# WL-CONTROL.net
KiCad netlist of a schematic drawn in Altium Designer
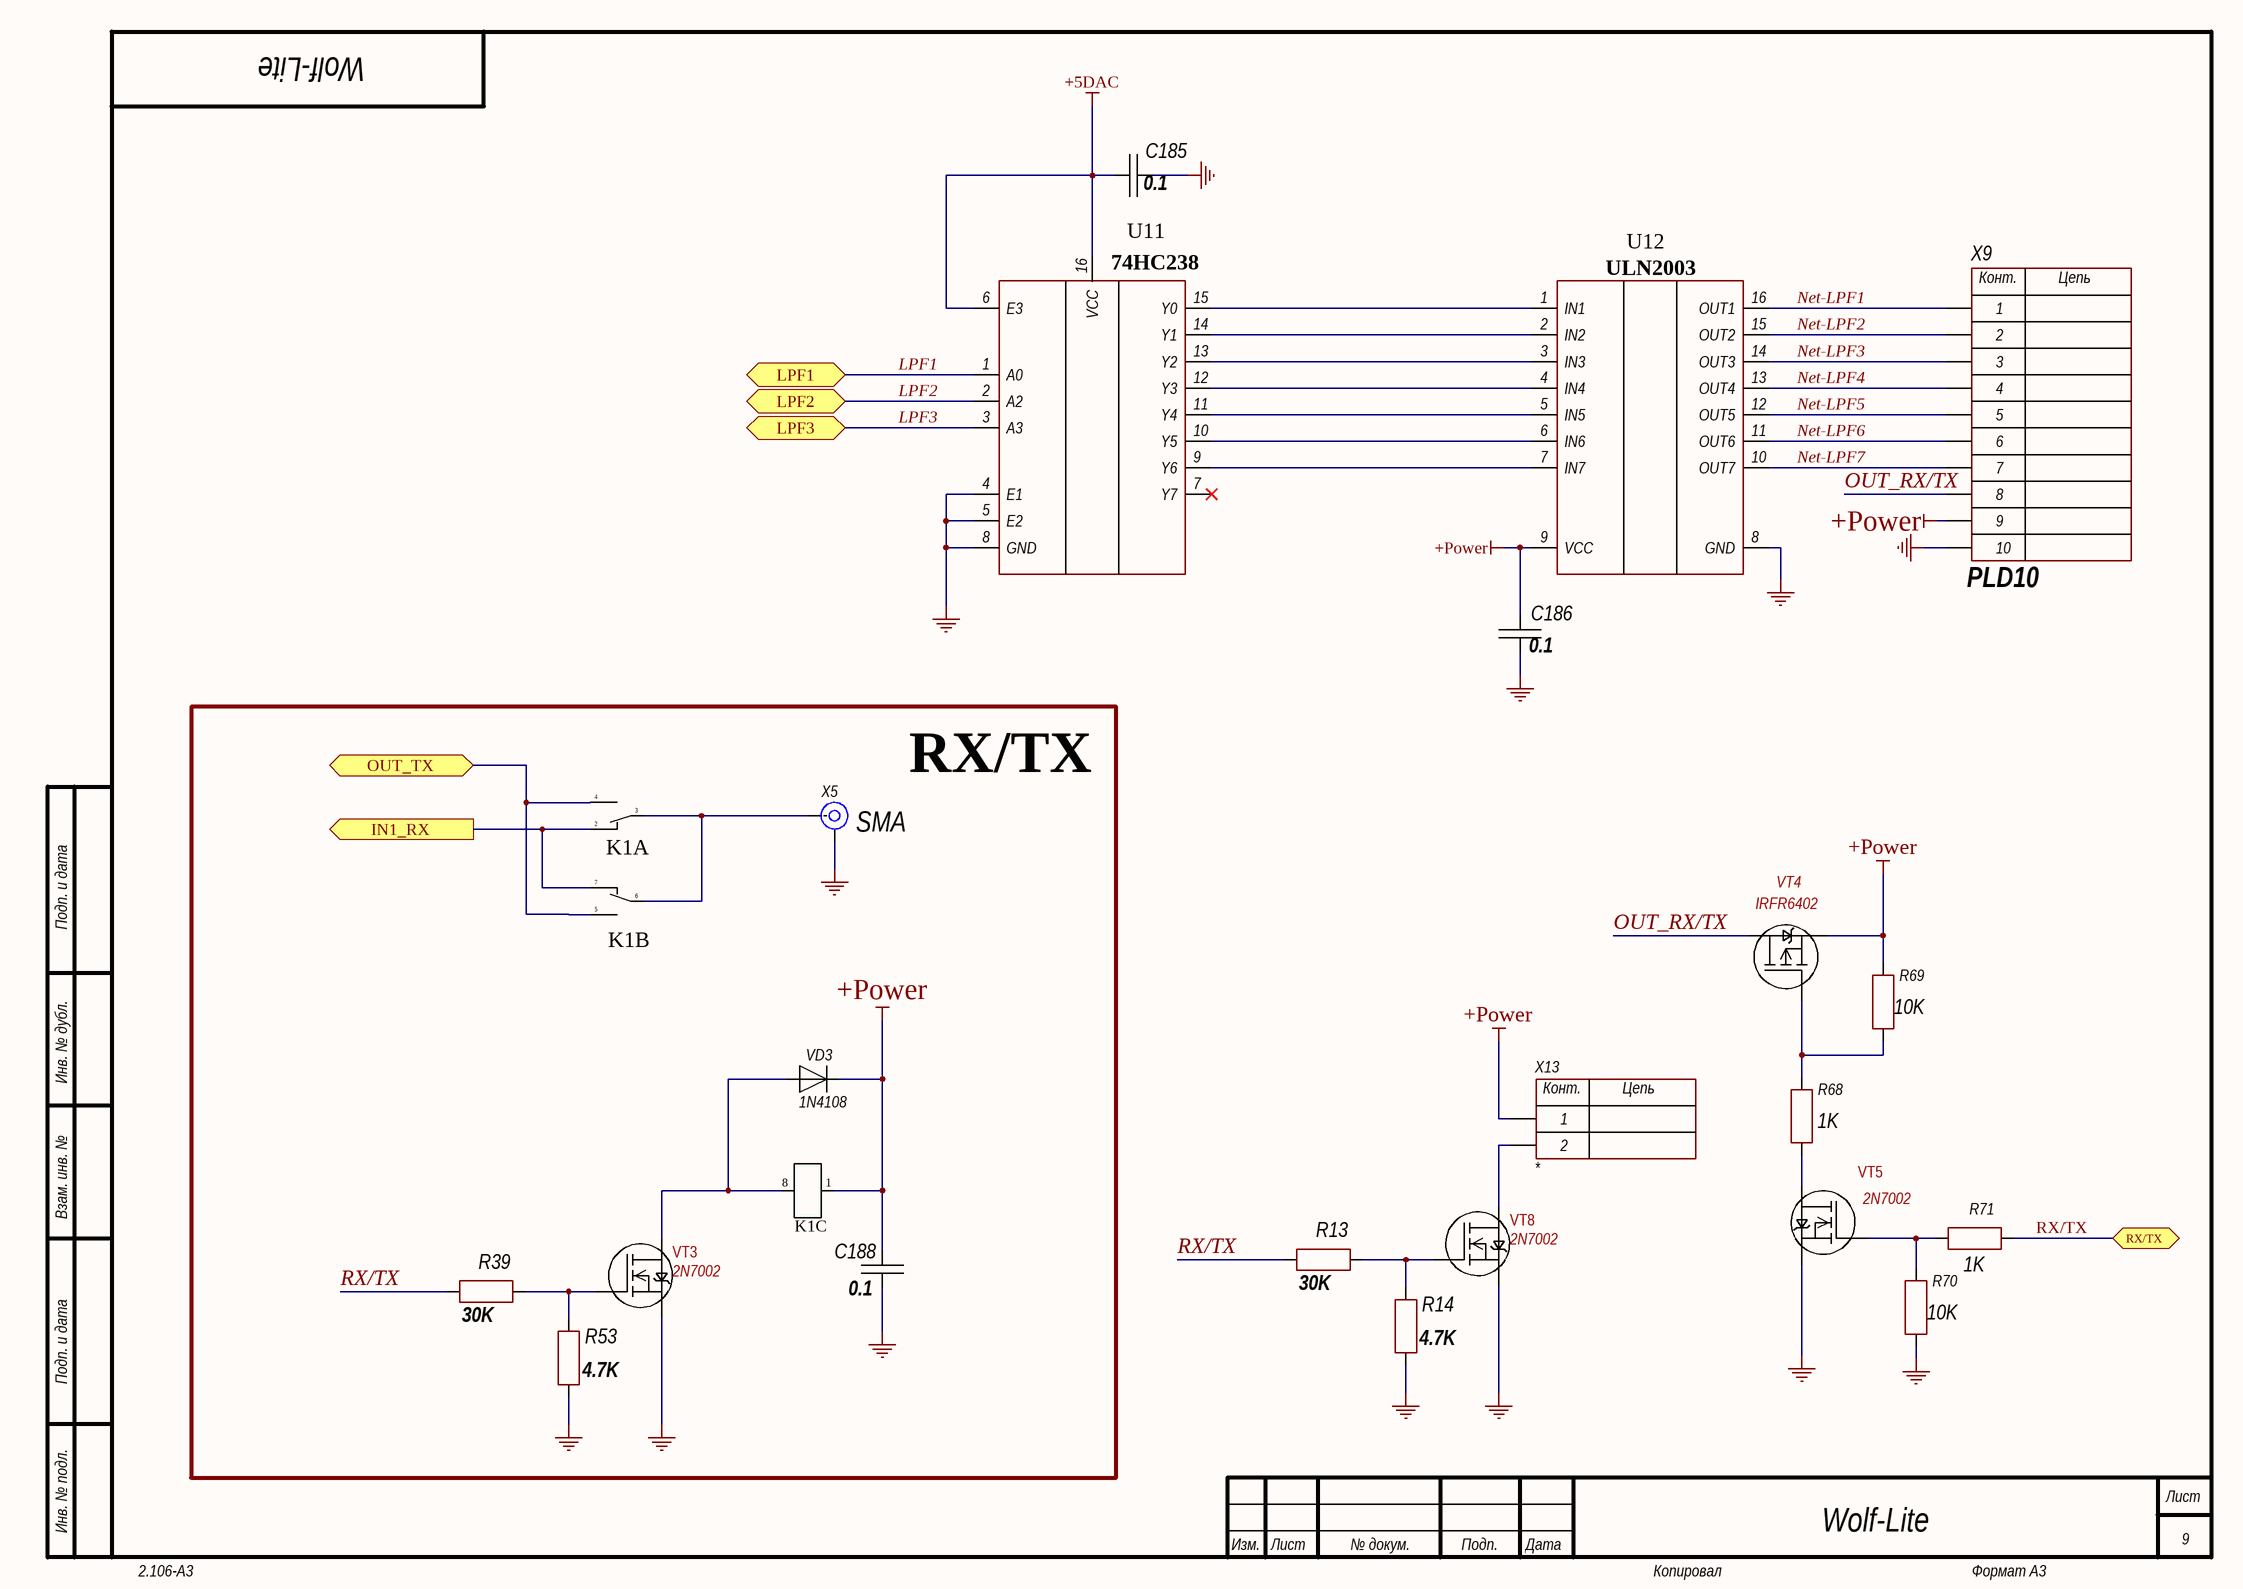
[diagram p0: WL-CONTROL.SchDoc]

(export (version "E")
  (design (tool "Eeschema 10.0.6"))
  (components
    (comp (ref "C185")
      (value "0.1")
      (footprint "standard:CH0805C")
      (libsource (lib "Discrete") (part "Capacitor"))
    )
    (comp (ref "C186")
      (value "0.1")
      (footprint "standard:CH0805C")
      (libsource (lib "Discrete") (part "Capacitor"))
    )
    (comp (ref "C188")
      (value "0.1")
      (footprint "standard:CH0805C")
      (libsource (lib "Discrete") (part "Capacitor"))
    )
    (comp (ref "K1") (value "IM06") (footprint "IMG06") (libsource (lib "") (part "IM06-1_1")))
    (comp (ref "R13")
      (value "30K")
      (footprint "standard:CH0805R")
      (libsource (lib "Discrete") (part "Resistor"))
    )
    (comp (ref "R14") (value "4.7K") (footprint "standard:CH0805R") (libsource (lib "") (part "Resistor_1")))
    (comp (ref "R39")
      (value "30K")
      (footprint "standard:CH0805R")
      (libsource (lib "Discrete") (part "Resistor"))
    )
    (comp (ref "R53") (value "4.7K") (footprint "standard:CH0805R") (libsource (lib "") (part "Resistor_1")))
    (comp (ref "R68") (value "1K") (footprint "standard:CH0805R") (libsource (lib "") (part "Resistor_1")))
    (comp (ref "R69") (value "10K") (footprint "standard:CH0805R") (libsource (lib "") (part "Resistor_1")))
    (comp (ref "R70") (value "10K") (footprint "standard:CH0805R") (libsource (lib "") (part "Resistor_1")))
    (comp (ref "R71")
      (value "1K")
      (footprint "standard:CH0805R")
      (libsource (lib "Discrete") (part "Resistor"))
    )
    (comp (ref "U11") (value "74HC238") (footprint "16-SOIC") (libsource (lib "Digital") (part "74HC238")))
    (comp (ref "U12")
      (value "ULN2003")
      (footprint "16-SOIC")
      (libsource (lib "Digital") (part "ULN2003_NEW"))
    )
    (comp (ref "VD3") (value "1N4108") (footprint "1N4148") (libsource (lib "Diods") (part "Diod")))
    (comp (ref "VT3")
      (value "2N7002")
      (footprint "SOT23_132")
      (libsource (lib "Transistor") (part "N-KANAL"))
    )
    (comp (ref "VT4")
      (value "IRFR6402")
      (footprint "SOT23_132")
      (libsource (lib "Transistor") (part "P-KANAL"))
    )
    (comp (ref "VT5") (value "2N7002") (footprint "SOT23_132") (libsource (lib "") (part "N-KANAL_1")))
    (comp (ref "VT8")
      (value "2N7002")
      (footprint "SOT23_132")
      (libsource (lib "Transistor") (part "N-KANAL"))
    )
    (comp (ref "X5")
      (value "SMA")
      (footprint "custom:CON: SMA")
      (description "RF")
      (libsource (lib "Connectors") (part "SMA"))
    )
    (comp (ref "X9")
      (value "PLD10")
      (footprint "custom:CON: PLD-10")
      (libsource (lib "Connectors") (part "10-Connector"))
    )
    (comp (ref "X13")
      (value "*")
      (footprint "custom:CON: PLS-2")
      (libsource (lib "Connectors") (part "2-Connector"))
    )
  )
  (nets
    (net (code "1") (name "+5DAC") (class "Default")
      (node (ref "C185") (pin "1") (pinfunction "1_1") (pintype "power_in"))
      (node (ref "U11") (pin "16") (pinfunction "VCC_16") (pintype "passive"))
      (node (ref "U11") (pin "6") (pinfunction "E3_6") (pintype "passive"))
    )
    (net (code "2") (name "+Power") (class "Default")
      (node (ref "C186") (pin "2") (pinfunction "2_2") (pintype "power_in"))
      (node (ref "C188") (pin "1") (pinfunction "1_1") (pintype "power_in"))
      (node (ref "K1") (pin "1") (pintype "passive"))
      (node (ref "R69") (pin "2") (pinfunction "2_2") (pintype "passive"))
      (node (ref "U12") (pin "9") (pinfunction "VCC_9") (pintype "passive"))
      (node (ref "VD3") (pin "2") (pinfunction "2_2") (pintype "passive"))
      (node (ref "VT4") (pin "2") (pinfunction "I_2") (pintype "passive"))
      (node (ref "X13") (pin "1") (pinfunction "1_1") (pintype "passive"))
      (node (ref "X9") (pin "9") (pinfunction "9_9") (pintype "power_in"))
    )
    (net (code "3") (name "/IN1_RX") (class "Default")
      (node (ref "K1") (pin "2") (pintype "passive"))
      (node (ref "K1") (pin "7") (pintype "passive"))
    )
    (net (code "4") (name "/LPF1") (class "Default")
      (node (ref "U11") (pin "1") (pinfunction "A0_1") (pintype "passive"))
    )
    (net (code "5") (name "/LPF2") (class "Default")
      (node (ref "U11") (pin "2") (pinfunction "A2_2") (pintype "passive"))
    )
    (net (code "6") (name "/LPF3") (class "Default")
      (node (ref "U11") (pin "3") (pinfunction "A3_3") (pintype "passive"))
    )
    (net (code "7") (name "/Net-LPF1") (class "Default")
      (node (ref "U12") (pin "16") (pinfunction "OUT1_16") (pintype "passive"))
      (node (ref "X9") (pin "1") (pinfunction "1_1") (pintype "passive"))
    )
    (net (code "8") (name "/Net-LPF2") (class "Default")
      (node (ref "U12") (pin "15") (pinfunction "OUT2_15") (pintype "passive"))
      (node (ref "X9") (pin "2") (pinfunction "2_2") (pintype "passive"))
    )
    (net (code "9") (name "/Net-LPF3") (class "Default")
      (node (ref "U12") (pin "14") (pinfunction "OUT3_14") (pintype "passive"))
      (node (ref "X9") (pin "3") (pinfunction "3_3") (pintype "power_in"))
    )
    (net (code "10") (name "/Net-LPF4") (class "Default")
      (node (ref "U12") (pin "13") (pinfunction "OUT4_13") (pintype "passive"))
      (node (ref "X9") (pin "4") (pinfunction "4_4") (pintype "power_in"))
    )
    (net (code "11") (name "/Net-LPF5") (class "Default")
      (node (ref "U12") (pin "12") (pinfunction "OUT5_12") (pintype "passive"))
      (node (ref "X9") (pin "5") (pinfunction "5_5") (pintype "power_in"))
    )
    (net (code "12") (name "/Net-LPF6") (class "Default")
      (node (ref "U12") (pin "11") (pinfunction "OUT6_11") (pintype "passive"))
      (node (ref "X9") (pin "6") (pinfunction "6_6") (pintype "power_in"))
    )
    (net (code "13") (name "/Net-LPF7") (class "Default")
      (node (ref "U12") (pin "10") (pinfunction "OUT7_10") (pintype "passive"))
      (node (ref "X9") (pin "7") (pinfunction "7_7") (pintype "power_in"))
    )
    (net (code "14") (name "/OUT_RX{slash}TX") (class "Default")
      (node (ref "VT4") (pin "3") (pinfunction "Сток(Drain)_3") (pintype "passive"))
      (node (ref "X9") (pin "8") (pinfunction "8_8") (pintype "power_in"))
    )
    (net (code "15") (name "/OUT_TX") (class "Default")
      (node (ref "K1") (pin "4") (pintype "passive"))
      (node (ref "K1") (pin "5") (pintype "passive"))
    )
    (net (code "16") (name "/RX{slash}TX") (class "Default")
      (node (ref "R13") (pin "2") (pinfunction "2_2") (pintype "passive"))
      (node (ref "R39") (pin "2") (pinfunction "2_2") (pintype "passive"))
      (node (ref "R71") (pin "1") (pinfunction "1_1") (pintype "passive"))
    )
    (net (code "17") (name "GND") (class "Default")
      (node (ref "C185") (pin "2") (pinfunction "2_2") (pintype "power_in"))
      (node (ref "C186") (pin "1") (pinfunction "1_1") (pintype "power_in"))
      (node (ref "C188") (pin "2") (pinfunction "2_2") (pintype "power_in"))
      (node (ref "R14") (pin "1") (pinfunction "1_1") (pintype "passive"))
      (node (ref "R53") (pin "1") (pinfunction "1_1") (pintype "passive"))
      (node (ref "R70") (pin "1") (pinfunction "1_1") (pintype "passive"))
      (node (ref "U11") (pin "4") (pinfunction "E1_4") (pintype "passive"))
      (node (ref "U11") (pin "5") (pinfunction "E2_5") (pintype "passive"))
      (node (ref "U11") (pin "8") (pinfunction "GND_8") (pintype "passive"))
      (node (ref "U12") (pin "8") (pinfunction "GND_8") (pintype "passive"))
      (node (ref "VT3") (pin "2") (pinfunction "I_2") (pintype "passive"))
      (node (ref "VT5") (pin "2") (pinfunction "I_2") (pintype "passive"))
      (node (ref "VT8") (pin "2") (pinfunction "I_2") (pintype "passive"))
      (node (ref "X5") (pin "2") (pinfunction "IN_2") (pintype "passive"))
      (node (ref "X9") (pin "10") (pinfunction "10_10") (pintype "power_in"))
    )
    (net (code "18") (name "Net-(K1-Pad3)") (class "Default")
      (node (ref "K1") (pin "3") (pintype "passive"))
      (node (ref "K1") (pin "6") (pintype "passive"))
      (node (ref "X5") (pin "1") (pinfunction "IN_1") (pintype "passive"))
    )
    (net (code "19") (name "Net-(U11-Y0)") (class "Default")
      (node (ref "U11") (pin "15") (pinfunction "Y0_15") (pintype "passive"))
      (node (ref "U12") (pin "1") (pinfunction "IN1_1") (pintype "passive"))
    )
    (net (code "20") (name "Net-(U11-Y1)") (class "Default")
      (node (ref "U11") (pin "14") (pinfunction "Y1_14") (pintype "passive"))
      (node (ref "U12") (pin "2") (pinfunction "IN2_2") (pintype "passive"))
    )
    (net (code "21") (name "Net-(U11-Y2)") (class "Default")
      (node (ref "U11") (pin "13") (pinfunction "Y2_13") (pintype "passive"))
      (node (ref "U12") (pin "3") (pinfunction "IN3_3") (pintype "passive"))
    )
    (net (code "22") (name "Net-(U11-Y3)") (class "Default")
      (node (ref "U11") (pin "12") (pinfunction "Y3_12") (pintype "passive"))
      (node (ref "U12") (pin "4") (pinfunction "IN4_4") (pintype "passive"))
    )
    (net (code "23") (name "Net-(U11-Y4)") (class "Default")
      (node (ref "U11") (pin "11") (pinfunction "Y4_11") (pintype "passive"))
      (node (ref "U12") (pin "5") (pinfunction "IN5_5") (pintype "passive"))
    )
    (net (code "24") (name "Net-(U11-Y5)") (class "Default")
      (node (ref "U11") (pin "10") (pinfunction "Y5_10") (pintype "passive"))
      (node (ref "U12") (pin "6") (pinfunction "IN6_6") (pintype "passive"))
    )
    (net (code "25") (name "Net-(U11-Y6)") (class "Default")
      (node (ref "U11") (pin "9") (pinfunction "Y6_9") (pintype "passive"))
      (node (ref "U12") (pin "7") (pinfunction "IN7_7") (pintype "passive"))
    )
    (net (code "26") (name "Net-(VT3-Затвор(Gate))") (class "Default")
      (node (ref "R39") (pin "1") (pinfunction "1_1") (pintype "passive"))
      (node (ref "R53") (pin "2") (pinfunction "2_2") (pintype "passive"))
      (node (ref "VT3") (pin "1") (pinfunction "Затвор(Gate)_1") (pintype "passive"))
    )
    (net (code "27") (name "Net-(VT3-Сток(Drain))") (class "Default")
      (node (ref "K1") (pin "8") (pintype "passive"))
      (node (ref "VD3") (pin "1") (pinfunction "1_1") (pintype "passive"))
      (node (ref "VT3") (pin "3") (pinfunction "Сток(Drain)_3") (pintype "passive"))
    )
    (net (code "28") (name "Net-(VT4-Затвор(Gate))") (class "Default")
      (node (ref "R68") (pin "2") (pinfunction "2_2") (pintype "passive"))
      (node (ref "R69") (pin "1") (pinfunction "1_1") (pintype "passive"))
      (node (ref "VT4") (pin "1") (pinfunction "Затвор(Gate)_1") (pintype "passive"))
    )
    (net (code "29") (name "Net-(VT5-Затвор(Gate))") (class "Default")
      (node (ref "R70") (pin "2") (pinfunction "2_2") (pintype "passive"))
      (node (ref "R71") (pin "2") (pinfunction "2_2") (pintype "passive"))
      (node (ref "VT5") (pin "1") (pinfunction "Затвор(Gate)_1") (pintype "passive"))
    )
    (net (code "30") (name "Net-(VT5-Сток(Drain))") (class "Default")
      (node (ref "R68") (pin "1") (pinfunction "1_1") (pintype "passive"))
      (node (ref "VT5") (pin "3") (pinfunction "Сток(Drain)_3") (pintype "passive"))
    )
    (net (code "31") (name "Net-(VT8-Затвор(Gate))") (class "Default")
      (node (ref "R13") (pin "1") (pinfunction "1_1") (pintype "passive"))
      (node (ref "R14") (pin "2") (pinfunction "2_2") (pintype "passive"))
      (node (ref "VT8") (pin "1") (pinfunction "Затвор(Gate)_1") (pintype "passive"))
    )
    (net (code "32") (name "Net-(VT8-Сток(Drain))") (class "Default")
      (node (ref "VT8") (pin "3") (pinfunction "Сток(Drain)_3") (pintype "passive"))
      (node (ref "X13") (pin "2") (pinfunction "2_2") (pintype "passive"))
    )
    (net (code "33") (name "unconnected-(U11-Y7-Pad7)") (class "Default")
      (node (ref "U11") (pin "7") (pinfunction "Y7_7") (pintype "passive+no_connect"))
    )
  )
)
